# Stepper_Driver_Quark.net
KiCad netlist of a schematic drawn in Altium Designer
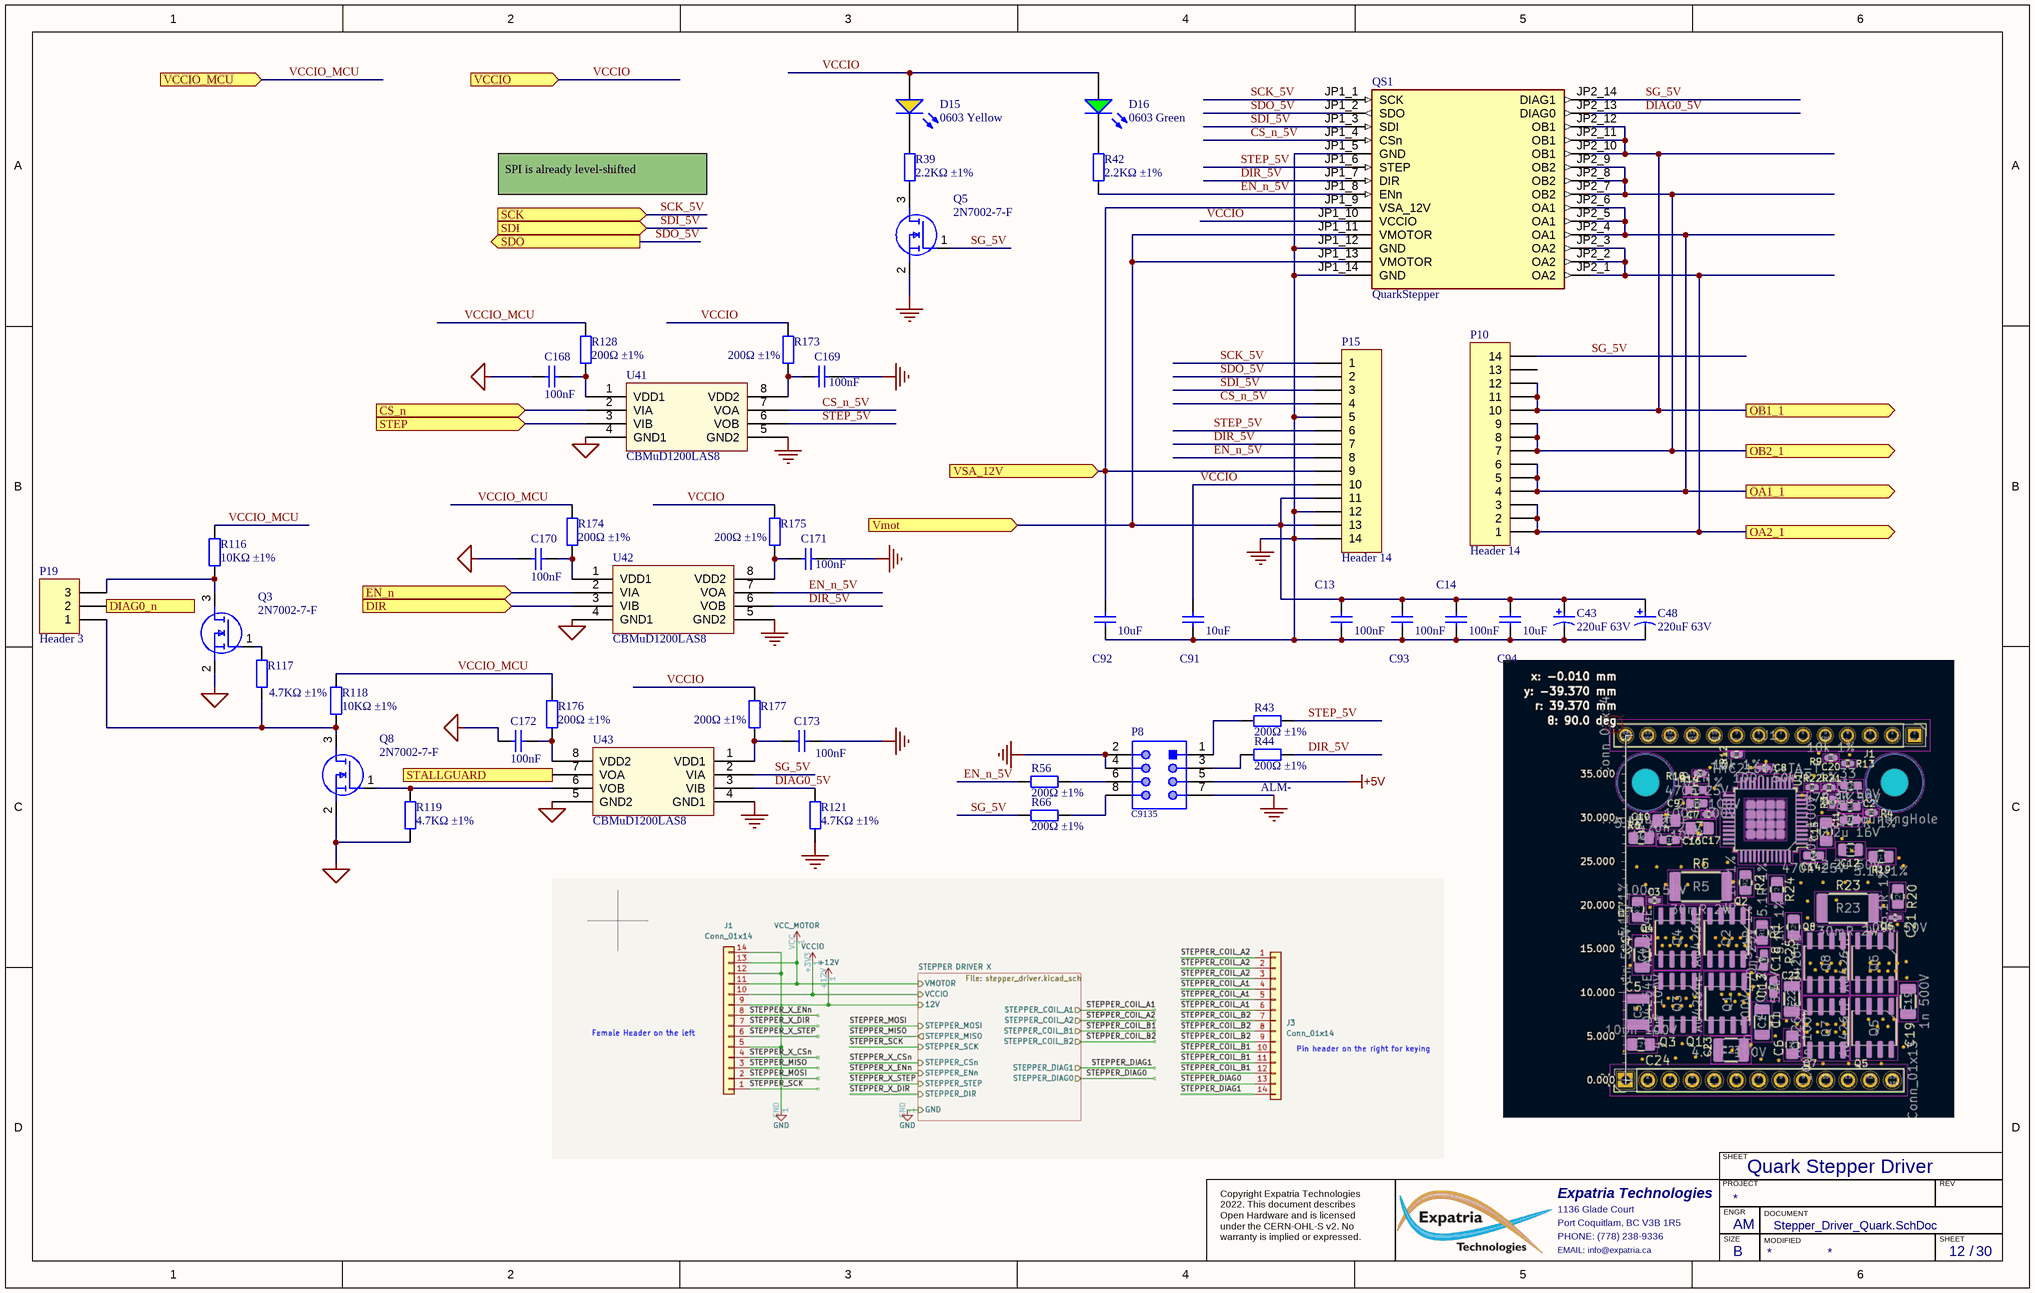
[diagram p0: Stepper_Driver_Quark.SchDoc]

(export (version "E")
  (design (tool "Eeschema 10.0.6"))
  (components
    (comp (ref "C13")
      (value "100nF")
      (footprint "0603_C")
      (description "Chip capacitors")
      (fields
        (field (name "MANUFACTURER") "YAGEO")
        (field (name "MANUFACTURER PART NUMBER") "CC0603KRX7R9BB104")
      )
      (libsource (lib "Cap") (part "0603 100nF (104) 10% 50V"))
    )
    (comp (ref "C14")
      (value "100nF")
      (footprint "0603_C")
      (description "Chip capacitors")
      (fields
        (field (name "MANUFACTURER") "YAGEO")
        (field (name "MANUFACTURER PART NUMBER") "CC0603KRX7R9BB104")
      )
      (libsource (lib "Cap") (part "0603 100nF (104) 10% 50V"))
    )
    (comp (ref "C43")
      (value "220uF 63V")
      (footprint "PNSC-FK-V-H13_V")
      (fields (field (name "MANUFACTURER") "Panasonic"))
      (libsource (lib "Altium Content Vault") (part "CAP-P-2"))
    )
    (comp (ref "C48")
      (value "220uF 63V")
      (footprint "PNSC-FK-V-H13_V")
      (fields (field (name "MANUFACTURER") "Panasonic"))
      (libsource (lib "Altium Content Vault") (part "CAP-P-2"))
    )
    (comp (ref "C91")
      (value "10uF")
      (footprint "0805_C")
      (description "Chip capacitors")
      (fields
        (field (name "MANUFACTURER") "Samsung Electro-Mechanics")
        (field (name "PARTNUMBER") "CL21A106KAYNNNE")
      )
      (libsource (lib "Cap") (part "0805 10uF (106) 10% 25V"))
    )
    (comp (ref "C92")
      (value "10uF")
      (footprint "0805_C")
      (description "Chip capacitors")
      (fields
        (field (name "MANUFACTURER") "Samsung Electro-Mechanics")
        (field (name "PARTNUMBER") "CL21A106KAYNNNE")
      )
      (libsource (lib "Cap") (part "0805 10uF (106) 10% 25V"))
    )
    (comp (ref "C93")
      (value "100nF")
      (footprint "0603_C")
      (description "Chip capacitors")
      (fields
        (field (name "MANUFACTURER") "YAGEO")
        (field (name "MANUFACTURER PART NUMBER") "CC0603KRX7R9BB104")
      )
      (libsource (lib "Cap") (part "0603 100nF (104) 10% 50V"))
    )
    (comp (ref "C94")
      (value "10uF")
      (footprint "0805_C")
      (description "Chip capacitors")
      (fields
        (field (name "MANUFACTURER") "Samsung Electro-Mechanics")
        (field (name "PARTNUMBER") "CL21A106KAYNNNE")
      )
      (libsource (lib "Cap") (part "0805 10uF (106) 10% 25V"))
    )
    (comp (ref "C168")
      (value "100nF")
      (footprint "0603_C")
      (description "Chip capacitors")
      (fields (field (name "MANUFACTURER") "YAGEO") (field (name "PARTNUMBER") "CC0603KRX7R9BB104"))
      (libsource (lib "Cap") (part "0603 100nF (104) 10% 50V"))
    )
    (comp (ref "C169")
      (value "100nF")
      (footprint "0603_C")
      (description "Chip capacitors")
      (fields (field (name "MANUFACTURER") "YAGEO") (field (name "PARTNUMBER") "CC0603KRX7R9BB104"))
      (libsource (lib "Cap") (part "0603 100nF (104) 10% 50V"))
    )
    (comp (ref "C170")
      (value "100nF")
      (footprint "0603_C")
      (description "Chip capacitors")
      (fields (field (name "MANUFACTURER") "YAGEO") (field (name "PARTNUMBER") "CC0603KRX7R9BB104"))
      (libsource (lib "Cap") (part "0603 100nF (104) 10% 50V"))
    )
    (comp (ref "C171")
      (value "100nF")
      (footprint "0603_C")
      (description "Chip capacitors")
      (fields (field (name "MANUFACTURER") "YAGEO") (field (name "PARTNUMBER") "CC0603KRX7R9BB104"))
      (libsource (lib "Cap") (part "0603 100nF (104) 10% 50V"))
    )
    (comp (ref "C172")
      (value "100nF")
      (footprint "0603_C")
      (description "Chip capacitors")
      (fields (field (name "MANUFACTURER") "YAGEO") (field (name "PARTNUMBER") "CC0603KRX7R9BB104"))
      (libsource (lib "Cap") (part "0603 100nF (104) 10% 50V"))
    )
    (comp (ref "C173")
      (value "100nF")
      (footprint "0603_C")
      (description "Chip capacitors")
      (fields (field (name "MANUFACTURER") "YAGEO") (field (name "PARTNUMBER") "CC0603KRX7R9BB104"))
      (libsource (lib "Cap") (part "0603 100nF (104) 10% 50V"))
    )
    (comp (ref "D15")
      (value "0603 Yellow")
      (footprint "0603_LED_S1")
      (description "LED")
      (libsource (lib "LED") (part "0603 LED Yellow"))
    )
    (comp (ref "D16")
      (value "0603 Green")
      (footprint "0603_LED_S1")
      (description "LED")
      (libsource (lib "LED") (part "0603 LED Green"))
    )
    (comp (ref "P8")
      (value "C9135")
      (footprint "61200821621")
      (description "Male Box Header WR-BHD, THT, Vertical, pitch 2.54 mm, 8 pins")
      (fields (field (name "MANUFACTURER") "Wurth Elektronik") (field (name "PUBLISHER") "WurthElektronik"))
      (libsource (lib "PrintNC_GRBLHAL_Breakout") (part "WE-CN-2P-M-R8"))
    )
    (comp (ref "P10")
      (value "Header 14")
      (footprint "HDR1X14")
      (description "Header, 14-Pin")
      (fields (field (name "PUBLISHER") "Altium Limited"))
      (libsource (lib "") (part "Header 14_1"))
    )
    (comp (ref "P15")
      (value "Header 14")
      (footprint "HDR1X14")
      (description "Socket, 14-Pin")
      (fields (field (name "PUBLISHER") "Altium Limited"))
      (libsource (lib "Miscellaneous Connectors") (part "Header 14"))
    )
    (comp (ref "P19")
      (value "Header 3")
      (footprint "HDR1X3")
      (description "Header, 3-Pin")
      (fields (field (name "PUBLISHER") "Altium Limited"))
      (libsource (lib "Miscellaneous Connectors") (part "Header 3"))
    )
    (comp (ref "Q3")
      (value "2N7002-7-F")
      (footprint "SOT-23(SOT-23-3)")
      (description "60V 115mA 7.5Ω@5V,50mA 370mW N Channel SOT-23 MOSFETs ROHS")
      (fields (field (name "MANUFACTURER") "Diodes Inc.") (field (name "MOUSER PART NUMBER") "621-2N7002-F"))
      (libsource (lib "Sienci_Labs") (part "2N7002-7-F"))
    )
    (comp (ref "Q5")
      (value "2N7002-7-F")
      (footprint "SOT-23(SOT-23-3)")
      (description "60V 115mA 7.5Ω@5V,50mA 370mW N Channel SOT-23 MOSFETs ROHS")
      (fields (field (name "MANUFACTURER") "Diodes Inc.") (field (name "MOUSER PART NUMBER") "621-2N7002-F"))
      (libsource (lib "Sienci_Labs") (part "2N7002-7-F"))
    )
    (comp (ref "Q8")
      (value "2N7002-7-F")
      (footprint "SOT-23(SOT-23-3)")
      (description "60V 115mA 7.5Ω@5V,50mA 370mW N Channel SOT-23 MOSFETs ROHS")
      (fields (field (name "MANUFACTURER") "Diodes Inc.") (field (name "MOUSER PART NUMBER") "621-2N7002-F"))
      (libsource (lib "Sienci_Labs") (part "2N7002-7-F"))
    )
    (comp (ref "QS1")
      (value "QuarkStepper")
      (footprint "QuarkStepperDriver")
      (description "Open source TMC2160 module")
      (fields
        (field (name "DIGI-KEY_PART_NUMBER") "1460-TMC2208SILENTSTEPSTICK-ND")
        (field (name "MF") "Trinamic Motion")
      )
      (libsource (lib "Universal_CNC_Breakout") (part "Quark_2160"))
    )
    (comp (ref "R39")
      (value "2.2KΩ ±1%")
      (footprint "0603_R")
      (description "Chip resistor")
      (fields (field (name "MANUFACTURER") "Uniroyal Elec") (field (name "POWER") "1/10W"))
      (libsource (lib "RES") (part "0603 2.2K (2201) 1%"))
    )
    (comp (ref "R42")
      (value "2.2KΩ ±1%")
      (footprint "0603_R")
      (description "Chip resistor")
      (fields (field (name "MANUFACTURER") "Uniroyal Elec") (field (name "POWER") "1/10W"))
      (libsource (lib "RES") (part "0603 2.2K (2201) 1%"))
    )
    (comp (ref "R43")
      (value "200Ω ±1%")
      (footprint "0603_R")
      (description "Chip resistor")
      (fields (field (name "MANUFACTURER") "Uniroyal Elec") (field (name "PARTNUMBER") "0603WAF2000T5E"))
      (libsource (lib "") (part "0603 200R (2000) 1%_1"))
    )
    (comp (ref "R44")
      (value "200Ω ±1%")
      (footprint "0603_R")
      (description "Chip resistor")
      (fields (field (name "MANUFACTURER") "Uniroyal Elec") (field (name "PARTNUMBER") "0603WAF2000T5E"))
      (libsource (lib "") (part "0603 200R (2000) 1%_1"))
    )
    (comp (ref "R56")
      (value "200Ω ±1%")
      (footprint "0603_R")
      (description "Chip resistor")
      (fields (field (name "MANUFACTURER") "Uniroyal Elec") (field (name "PARTNUMBER") "0603WAF2000T5E"))
      (libsource (lib "") (part "0603 200R (2000) 1%_1"))
    )
    (comp (ref "R66")
      (value "200Ω ±1%")
      (footprint "0603_R")
      (description "Chip resistor")
      (fields (field (name "MANUFACTURER") "Uniroyal Elec") (field (name "PARTNUMBER") "0603WAF2000T5E"))
      (libsource (lib "") (part "0603 200R (2000) 1%_1"))
    )
    (comp (ref "R116")
      (value "10KΩ ±1%")
      (footprint "0603_R")
      (description "Chip resistor")
      (fields (field (name "MANUFACTURER") "Uniroyal Elec") (field (name "PARTNUMBER") "0603WAF1002T5E"))
      (libsource (lib "RES") (part "0603 10K (1002) 1%"))
    )
    (comp (ref "R117")
      (value "4.7KΩ ±1%")
      (footprint "0603_R")
      (description "Chip resistor")
      (fields (field (name "MANUFACTURER") "Uniroyal Elec") (field (name "PARTNUMBER") "0603WAF4701T5E"))
      (libsource (lib "RES") (part "0603 4.7K (4701) 1%"))
    )
    (comp (ref "R118")
      (value "10KΩ ±1%")
      (footprint "0603_R")
      (description "Chip resistor")
      (fields (field (name "MANUFACTURER") "Uniroyal Elec") (field (name "PARTNUMBER") "0603WAF1002T5E"))
      (libsource (lib "RES") (part "0603 10K (1002) 1%"))
    )
    (comp (ref "R119")
      (value "4.7KΩ ±1%")
      (footprint "0603_R")
      (description "Chip resistor")
      (fields (field (name "MANUFACTURER") "Uniroyal Elec") (field (name "PARTNUMBER") "0603WAF4701T5E"))
      (libsource (lib "RES") (part "0603 4.7K (4701) 1%"))
    )
    (comp (ref "R121")
      (value "4.7KΩ ±1%")
      (footprint "0603_R")
      (description "Chip resistor")
      (fields (field (name "MANUFACTURER") "Uniroyal Elec") (field (name "PARTNUMBER") "0603WAF4701T5E"))
      (libsource (lib "RES") (part "0603 4.7K (4701) 1%"))
    )
    (comp (ref "R128")
      (value "200Ω ±1%")
      (footprint "0603_R")
      (description "Chip resistor")
      (fields (field (name "MANUFACTURER") "Uniroyal Elec") (field (name "PARTNUMBER") "0603WAF2000T5E"))
      (libsource (lib "RES") (part "0603 200R (2000) 1%"))
    )
    (comp (ref "R173")
      (value "200Ω ±1%")
      (footprint "0603_R")
      (description "Chip resistor")
      (fields (field (name "MANUFACTURER") "Uniroyal Elec") (field (name "PARTNUMBER") "0603WAF2000T5E"))
      (libsource (lib "RES") (part "0603 200R (2000) 1%"))
    )
    (comp (ref "R174")
      (value "200Ω ±1%")
      (footprint "0603_R")
      (description "Chip resistor")
      (fields (field (name "MANUFACTURER") "Uniroyal Elec") (field (name "PARTNUMBER") "0603WAF2000T5E"))
      (libsource (lib "RES") (part "0603 200R (2000) 1%"))
    )
    (comp (ref "R175")
      (value "200Ω ±1%")
      (footprint "0603_R")
      (description "Chip resistor")
      (fields (field (name "MANUFACTURER") "Uniroyal Elec") (field (name "PARTNUMBER") "0603WAF2000T5E"))
      (libsource (lib "RES") (part "0603 200R (2000) 1%"))
    )
    (comp (ref "R176")
      (value "200Ω ±1%")
      (footprint "0603_R")
      (description "Chip resistor")
      (fields (field (name "MANUFACTURER") "Uniroyal Elec") (field (name "PARTNUMBER") "0603WAF2000T5E"))
      (libsource (lib "") (part "0603 200R (2000) 1%_2"))
    )
    (comp (ref "R177")
      (value "200Ω ±1%")
      (footprint "0603_R")
      (description "Chip resistor")
      (fields (field (name "MANUFACTURER") "Uniroyal Elec") (field (name "PARTNUMBER") "0603WAF2000T5E"))
      (libsource (lib "") (part "0603 200R (2000) 1%_2"))
    )
    (comp (ref "U41")
      (value "CBMuD1200LAS8")
      (footprint "SOIC-8_150mil")
      (description "Dual Channel Isolator")
      (libsource (lib "IC") (part "CBMuD1200LAS8"))
    )
    (comp (ref "U42")
      (value "CBMuD1200LAS8")
      (footprint "SOIC-8_150mil")
      (description "Dual Channel Isolator")
      (libsource (lib "IC") (part "CBMuD1200LAS8"))
    )
    (comp (ref "U43")
      (value "CBMuD1200LAS8")
      (footprint "SOIC-8_150mil")
      (description "Dual Channel Isolator")
      (libsource (lib "") (part "CBMuD1200LAS8_1"))
    )
  )
  (nets
    (net (code "1") (name "+5V") (class "Default")
      (node (ref "P8") (pin "5") (pinfunction "5_5") (pintype "passive"))
    )
    (net (code "2") (name "/CS_n") (class "Default")
      (node (ref "U41") (pin "2") (pinfunction "VIA_2") (pintype "passive"))
    )
    (net (code "3") (name "/CS_n_5V") (class "Default")
      (node (ref "P15") (pin "4") (pinfunction "4_4") (pintype "passive"))
      (node (ref "QS1") (pin "JP1_4") (pinfunction "CSn_JP1_4") (pintype "input"))
      (node (ref "U41") (pin "7") (pinfunction "VOA_7") (pintype "passive"))
    )
    (net (code "4") (name "/DIAG0_5V") (class "Default")
      (node (ref "QS1") (pin "JP2_13") (pinfunction "DIAG0_JP2_13") (pintype "output"))
      (node (ref "R121") (pin "2") (pinfunction "2_2") (pintype "passive"))
      (node (ref "U43") (pin "3") (pinfunction "VIB_3") (pintype "passive"))
    )
    (net (code "5") (name "/DIAG0_n") (class "Default")
      (node (ref "P19") (pin "2") (pinfunction "2_2") (pintype "passive"))
    )
    (net (code "6") (name "/DIR") (class "Default")
      (node (ref "U42") (pin "3") (pinfunction "VIB_3") (pintype "passive"))
    )
    (net (code "7") (name "/DIR_5V") (class "Default")
      (node (ref "P15") (pin "7") (pinfunction "7_7") (pintype "passive"))
      (node (ref "QS1") (pin "JP1_7") (pinfunction "DIR_JP1_7") (pintype "input"))
      (node (ref "R44") (pin "1") (pinfunction "1_1") (pintype "passive"))
      (node (ref "U42") (pin "6") (pinfunction "VOB_6") (pintype "passive"))
    )
    (net (code "8") (name "/EN_n") (class "Default")
      (node (ref "U42") (pin "2") (pinfunction "VIA_2") (pintype "passive"))
    )
    (net (code "9") (name "/EN_n_5V") (class "Default")
      (node (ref "P15") (pin "8") (pinfunction "8_8") (pintype "passive"))
      (node (ref "QS1") (pin "JP1_8") (pinfunction "ENn_JP1_8") (pintype "input"))
      (node (ref "R42") (pin "1") (pinfunction "1_1") (pintype "passive"))
      (node (ref "R56") (pin "2") (pinfunction "2_2") (pintype "passive"))
      (node (ref "U42") (pin "7") (pinfunction "VOA_7") (pintype "passive"))
    )
    (net (code "10") (name "/OA1_1") (class "Default")
      (node (ref "P10") (pin "4") (pinfunction "4_4") (pintype "passive"))
      (node (ref "P10") (pin "5") (pinfunction "5_5") (pintype "passive"))
      (node (ref "P10") (pin "6") (pinfunction "6_6") (pintype "passive"))
      (node (ref "QS1") (pin "JP2_4") (pinfunction "OA1_JP2_4") (pintype "output"))
      (node (ref "QS1") (pin "JP2_5") (pinfunction "OA1_JP2_5") (pintype "output"))
      (node (ref "QS1") (pin "JP2_6") (pinfunction "OA1_JP2_6") (pintype "output"))
    )
    (net (code "11") (name "/OA2_1") (class "Default")
      (node (ref "P10") (pin "1") (pinfunction "1_1") (pintype "passive"))
      (node (ref "P10") (pin "2") (pinfunction "2_2") (pintype "passive"))
      (node (ref "P10") (pin "3") (pinfunction "3_3") (pintype "passive"))
      (node (ref "QS1") (pin "JP2_1") (pinfunction "OA2_JP2_1") (pintype "output"))
      (node (ref "QS1") (pin "JP2_2") (pinfunction "OA2_JP2_2") (pintype "output"))
      (node (ref "QS1") (pin "JP2_3") (pinfunction "OA2_JP2_3") (pintype "output"))
    )
    (net (code "12") (name "/OB1_1") (class "Default")
      (node (ref "P10") (pin "10") (pinfunction "10_10") (pintype "passive"))
      (node (ref "P10") (pin "11") (pinfunction "11_11") (pintype "passive"))
      (node (ref "P10") (pin "12") (pinfunction "12_12") (pintype "passive"))
      (node (ref "QS1") (pin "JP2_10") (pinfunction "OB1_JP2_10") (pintype "output"))
      (node (ref "QS1") (pin "JP2_11") (pinfunction "OB1_JP2_11") (pintype "output"))
      (node (ref "QS1") (pin "JP2_12") (pinfunction "OB1_JP2_12") (pintype "output"))
    )
    (net (code "13") (name "/OB2_1") (class "Default")
      (node (ref "P10") (pin "7") (pinfunction "7_7") (pintype "passive"))
      (node (ref "P10") (pin "8") (pinfunction "8_8") (pintype "passive"))
      (node (ref "P10") (pin "9") (pinfunction "9_9") (pintype "passive"))
      (node (ref "QS1") (pin "JP2_7") (pinfunction "OB2_JP2_7") (pintype "output"))
      (node (ref "QS1") (pin "JP2_8") (pinfunction "OB2_JP2_8") (pintype "output"))
      (node (ref "QS1") (pin "JP2_9") (pinfunction "OB2_JP2_9") (pintype "output"))
    )
    (net (code "14") (name "/SCK_5V") (class "Default")
      (node (ref "P15") (pin "1") (pinfunction "1_1") (pintype "passive"))
      (node (ref "QS1") (pin "JP1_1") (pinfunction "SCK_JP1_1") (pintype "input"))
    )
    (net (code "15") (name "/SDI_5V") (class "Default")
      (node (ref "P15") (pin "3") (pinfunction "3_3") (pintype "passive"))
      (node (ref "QS1") (pin "JP1_3") (pinfunction "SDI_JP1_3") (pintype "input"))
    )
    (net (code "16") (name "/SDO_5V") (class "Default")
      (node (ref "P15") (pin "2") (pinfunction "2_2") (pintype "passive"))
      (node (ref "QS1") (pin "JP1_2") (pinfunction "SDO_JP1_2") (pintype "output"))
    )
    (net (code "17") (name "/SG_5V") (class "Default")
      (node (ref "P10") (pin "14") (pinfunction "14_14") (pintype "passive"))
      (node (ref "Q5") (pin "1") (pinfunction "G_1") (pintype "passive"))
      (node (ref "QS1") (pin "JP2_14") (pinfunction "DIAG1_JP2_14") (pintype "output"))
      (node (ref "R66") (pin "2") (pinfunction "2_2") (pintype "passive"))
      (node (ref "U43") (pin "2") (pinfunction "VIA_2") (pintype "passive"))
    )
    (net (code "18") (name "/STALLGUARD") (class "Default")
      (node (ref "U43") (pin "7") (pinfunction "VOA_7") (pintype "passive"))
    )
    (net (code "19") (name "/STEP") (class "Default")
      (node (ref "U41") (pin "3") (pinfunction "VIB_3") (pintype "passive"))
    )
    (net (code "20") (name "/STEP_5V") (class "Default")
      (node (ref "P15") (pin "6") (pinfunction "6_6") (pintype "passive"))
      (node (ref "QS1") (pin "JP1_6") (pinfunction "STEP_JP1_6") (pintype "input"))
      (node (ref "R43") (pin "1") (pinfunction "1_1") (pintype "passive"))
      (node (ref "U41") (pin "6") (pinfunction "VOB_6") (pintype "passive"))
    )
    (net (code "21") (name "/VCCIO") (class "Default")
      (node (ref "C91") (pin "2") (pinfunction "2_2") (pintype "passive"))
      (node (ref "D15") (pin "A") (pinfunction "A_A") (pintype "passive"))
      (node (ref "D16") (pin "A") (pinfunction "A_A") (pintype "passive"))
      (node (ref "P15") (pin "10") (pinfunction "10_10") (pintype "passive"))
      (node (ref "QS1") (pin "JP1_10") (pinfunction "VCCIO_JP1_10") (pintype "passive"))
      (node (ref "R173") (pin "2") (pinfunction "2_2") (pintype "passive"))
      (node (ref "R175") (pin "2") (pinfunction "2_2") (pintype "passive"))
      (node (ref "R177") (pin "2") (pinfunction "2_2") (pintype "passive"))
    )
    (net (code "22") (name "/VCCIO_MCU") (class "Default")
      (node (ref "R116") (pin "2") (pinfunction "2_2") (pintype "passive"))
      (node (ref "R118") (pin "2") (pinfunction "2_2") (pintype "passive"))
      (node (ref "R128") (pin "2") (pinfunction "2_2") (pintype "passive"))
      (node (ref "R174") (pin "2") (pinfunction "2_2") (pintype "passive"))
      (node (ref "R176") (pin "2") (pinfunction "2_2") (pintype "passive"))
    )
    (net (code "23") (name "/VSA_12V") (class "Default")
      (node (ref "C92") (pin "2") (pinfunction "2_2") (pintype "passive"))
      (node (ref "P15") (pin "9") (pinfunction "9_9") (pintype "passive"))
      (node (ref "QS1") (pin "JP1_9") (pinfunction "VSA_12V_JP1_9") (pintype "passive"))
    )
    (net (code "24") (name "/Vmot") (class "Default")
      (node (ref "C13") (pin "1") (pinfunction "1_1") (pintype "passive"))
      (node (ref "C14") (pin "1") (pinfunction "1_1") (pintype "passive"))
      (node (ref "C43") (pin "1") (pinfunction "1_1") (pintype "passive"))
      (node (ref "C48") (pin "1") (pinfunction "1_1") (pintype "passive"))
      (node (ref "C93") (pin "1") (pinfunction "1_1") (pintype "passive"))
      (node (ref "C94") (pin "2") (pinfunction "2_2") (pintype "passive"))
      (node (ref "P15") (pin "11") (pinfunction "11_11") (pintype "passive"))
      (node (ref "P15") (pin "13") (pinfunction "13_13") (pintype "passive"))
      (node (ref "QS1") (pin "JP1_11") (pinfunction "VMOTOR_JP1_11") (pintype "passive"))
      (node (ref "QS1") (pin "JP1_13") (pinfunction "VMOTOR_JP1_13") (pintype "passive"))
    )
    (net (code "25") (name "GND") (class "Default")
      (node (ref "C13") (pin "2") (pinfunction "2_2") (pintype "passive"))
      (node (ref "C14") (pin "2") (pinfunction "2_2") (pintype "passive"))
      (node (ref "C169") (pin "1") (pinfunction "1_1") (pintype "passive"))
      (node (ref "C171") (pin "1") (pinfunction "1_1") (pintype "passive"))
      (node (ref "C173") (pin "2") (pinfunction "2_2") (pintype "passive"))
      (node (ref "C43") (pin "2") (pinfunction "2_2") (pintype "passive"))
      (node (ref "C48") (pin "2") (pinfunction "2_2") (pintype "passive"))
      (node (ref "C91") (pin "1") (pinfunction "1_1") (pintype "passive"))
      (node (ref "C92") (pin "1") (pinfunction "1_1") (pintype "passive"))
      (node (ref "C93") (pin "2") (pinfunction "2_2") (pintype "passive"))
      (node (ref "C94") (pin "1") (pinfunction "1_1") (pintype "passive"))
      (node (ref "P15") (pin "12") (pinfunction "12_12") (pintype "passive"))
      (node (ref "P15") (pin "14") (pinfunction "14_14") (pintype "passive"))
      (node (ref "P15") (pin "5") (pinfunction "5_5") (pintype "passive"))
      (node (ref "P8") (pin "2") (pinfunction "2_2") (pintype "passive"))
      (node (ref "P8") (pin "4") (pinfunction "4_4") (pintype "passive"))
      (node (ref "P8") (pin "7") (pinfunction "7_7") (pintype "passive"))
      (node (ref "Q5") (pin "2") (pinfunction "S_2") (pintype "passive"))
      (node (ref "QS1") (pin "JP1_12") (pinfunction "GND_JP1_12") (pintype "passive"))
      (node (ref "QS1") (pin "JP1_14") (pinfunction "GND_JP1_14") (pintype "passive"))
      (node (ref "QS1") (pin "JP1_5") (pinfunction "GND_JP1_5") (pintype "passive"))
      (node (ref "R121") (pin "1") (pinfunction "1_1") (pintype "passive"))
      (node (ref "U41") (pin "5") (pinfunction "GND2_5") (pintype "passive"))
      (node (ref "U42") (pin "5") (pinfunction "GND2_5") (pintype "passive"))
      (node (ref "U43") (pin "4") (pinfunction "GND1_4") (pintype "passive"))
    )
    (net (code "26") (name "MCU_GND") (class "Default")
      (node (ref "C168") (pin "2") (pinfunction "2_2") (pintype "passive"))
      (node (ref "C170") (pin "2") (pinfunction "2_2") (pintype "passive"))
      (node (ref "C172") (pin "1") (pinfunction "1_1") (pintype "passive"))
      (node (ref "Q3") (pin "2") (pinfunction "S_2") (pintype "passive"))
      (node (ref "Q8") (pin "2") (pinfunction "S_2") (pintype "passive"))
      (node (ref "R119") (pin "1") (pinfunction "1_1") (pintype "passive"))
      (node (ref "U41") (pin "4") (pinfunction "GND1_4") (pintype "passive"))
      (node (ref "U42") (pin "4") (pinfunction "GND1_4") (pintype "passive"))
      (node (ref "U43") (pin "5") (pinfunction "GND2_5") (pintype "passive"))
    )
    (net (code "27") (name "Net-(D15-PadK)") (class "Default")
      (node (ref "D15") (pin "K") (pinfunction "K_K") (pintype "passive"))
      (node (ref "R39") (pin "2") (pinfunction "2_2") (pintype "passive"))
    )
    (net (code "28") (name "Net-(D16-PadK)") (class "Default")
      (node (ref "D16") (pin "K") (pinfunction "K_K") (pintype "passive"))
      (node (ref "R42") (pin "2") (pinfunction "2_2") (pintype "passive"))
    )
    (net (code "29") (name "Net-(P8-Pad1)") (class "Default")
      (node (ref "P8") (pin "1") (pinfunction "1_1") (pintype "passive"))
      (node (ref "R43") (pin "2") (pinfunction "2_2") (pintype "passive"))
    )
    (net (code "30") (name "Net-(P8-Pad3)") (class "Default")
      (node (ref "P8") (pin "3") (pinfunction "3_3") (pintype "passive"))
      (node (ref "R44") (pin "2") (pinfunction "2_2") (pintype "passive"))
    )
    (net (code "31") (name "Net-(P8-Pad6)") (class "Default")
      (node (ref "P8") (pin "6") (pinfunction "6_6") (pintype "passive"))
      (node (ref "R56") (pin "1") (pinfunction "1_1") (pintype "passive"))
    )
    (net (code "32") (name "Net-(P8-Pad8)") (class "Default")
      (node (ref "P8") (pin "8") (pinfunction "8_8") (pintype "passive"))
      (node (ref "R66") (pin "1") (pinfunction "1_1") (pintype "passive"))
    )
    (net (code "33") (name "Net-(Q3-D)") (class "Default")
      (node (ref "P19") (pin "3") (pinfunction "3_3") (pintype "passive"))
      (node (ref "Q3") (pin "3") (pinfunction "D_3") (pintype "passive"))
      (node (ref "R116") (pin "1") (pinfunction "1_1") (pintype "passive"))
    )
    (net (code "34") (name "Net-(Q3-G)") (class "Default")
      (node (ref "Q3") (pin "1") (pinfunction "G_1") (pintype "passive"))
      (node (ref "R117") (pin "2") (pinfunction "2_2") (pintype "passive"))
    )
    (net (code "35") (name "Net-(Q5-D)") (class "Default")
      (node (ref "Q5") (pin "3") (pinfunction "D_3") (pintype "passive"))
      (node (ref "R39") (pin "1") (pinfunction "1_1") (pintype "passive"))
    )
    (net (code "36") (name "Net-(Q8-D)") (class "Default")
      (node (ref "P19") (pin "1") (pinfunction "1_1") (pintype "passive"))
      (node (ref "Q8") (pin "3") (pinfunction "D_3") (pintype "passive"))
      (node (ref "R117") (pin "1") (pinfunction "1_1") (pintype "passive"))
      (node (ref "R118") (pin "1") (pinfunction "1_1") (pintype "passive"))
    )
    (net (code "37") (name "Net-(Q8-G)") (class "Default")
      (node (ref "Q8") (pin "1") (pinfunction "G_1") (pintype "passive"))
      (node (ref "R119") (pin "2") (pinfunction "2_2") (pintype "passive"))
      (node (ref "U43") (pin "6") (pinfunction "VOB_6") (pintype "passive"))
    )
    (net (code "38") (name "Net-(U41-VDD1)") (class "Default")
      (node (ref "C168") (pin "1") (pinfunction "1_1") (pintype "passive"))
      (node (ref "R128") (pin "1") (pinfunction "1_1") (pintype "passive"))
      (node (ref "U41") (pin "1") (pinfunction "VDD1_1") (pintype "passive"))
    )
    (net (code "39") (name "Net-(U41-VDD2)") (class "Default")
      (node (ref "C169") (pin "2") (pinfunction "2_2") (pintype "passive"))
      (node (ref "R173") (pin "1") (pinfunction "1_1") (pintype "passive"))
      (node (ref "U41") (pin "8") (pinfunction "VDD2_8") (pintype "passive"))
    )
    (net (code "40") (name "Net-(U42-VDD1)") (class "Default")
      (node (ref "C170") (pin "1") (pinfunction "1_1") (pintype "passive"))
      (node (ref "R174") (pin "1") (pinfunction "1_1") (pintype "passive"))
      (node (ref "U42") (pin "1") (pinfunction "VDD1_1") (pintype "passive"))
    )
    (net (code "41") (name "Net-(U42-VDD2)") (class "Default")
      (node (ref "C171") (pin "2") (pinfunction "2_2") (pintype "passive"))
      (node (ref "R175") (pin "1") (pinfunction "1_1") (pintype "passive"))
      (node (ref "U42") (pin "8") (pinfunction "VDD2_8") (pintype "passive"))
    )
    (net (code "42") (name "Net-(U43-VDD1)") (class "Default")
      (node (ref "C173") (pin "1") (pinfunction "1_1") (pintype "passive"))
      (node (ref "R177") (pin "1") (pinfunction "1_1") (pintype "passive"))
      (node (ref "U43") (pin "1") (pinfunction "VDD1_1") (pintype "passive"))
    )
    (net (code "43") (name "Net-(U43-VDD2)") (class "Default")
      (node (ref "C172") (pin "2") (pinfunction "2_2") (pintype "passive"))
      (node (ref "R176") (pin "1") (pinfunction "1_1") (pintype "passive"))
      (node (ref "U43") (pin "8") (pinfunction "VDD2_8") (pintype "passive"))
    )
    (net (code "44") (name "unconnected-(P10-Pad13)") (class "Default")
      (node (ref "P10") (pin "13") (pinfunction "13_13") (pintype "passive"))
    )
  )
)
